# card.net
KiCad netlist of a schematic drawn in EasyEDA Pro
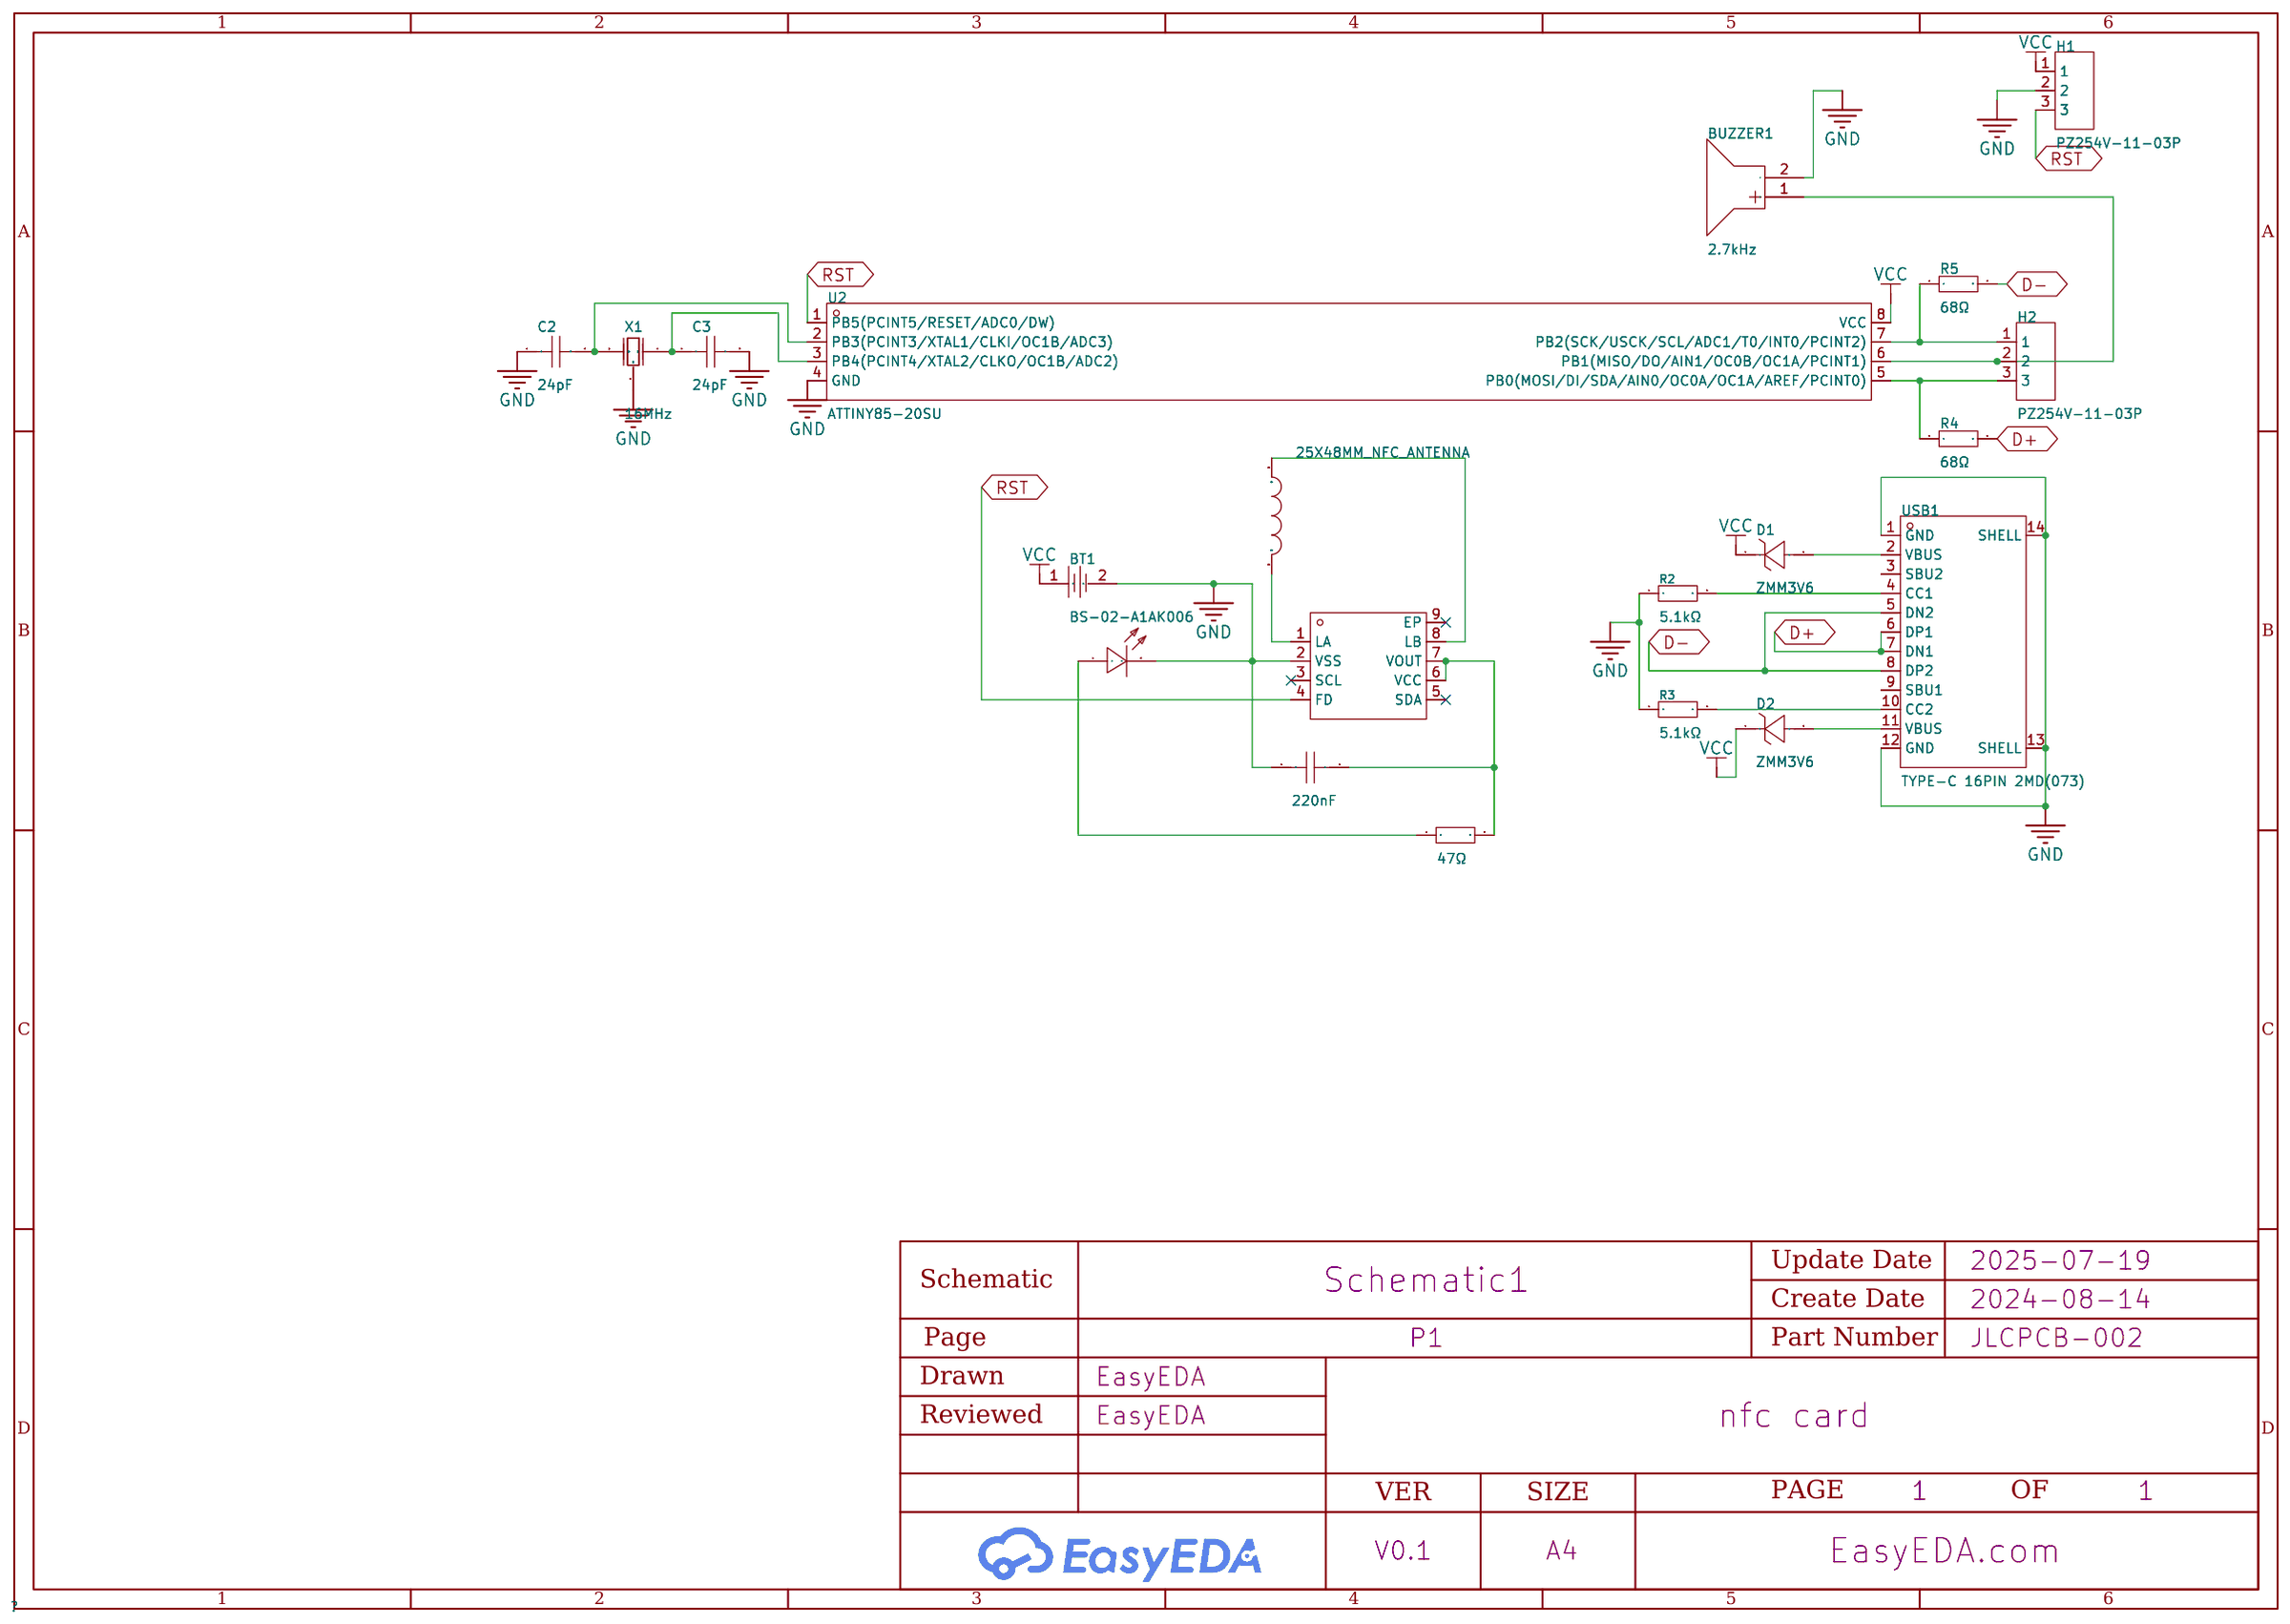
[diagram p0: schematic sheet]

(export (version "E")
  (design (tool "Eeschema 10.0.6"))
  (components
    (comp (ref "1") (value "25X48MM_NFC_ANTENNA") (libsource (lib "easyedapro") (part "25X48MM_NFC_ANTENNA")))
    (comp (ref "BT1")
      (value "BS-02-A1AK006")
      (footprint "easyedapro:BAT-TH_BS-02-A1AK006")
      (fields (field (name "Manufacturer") "MYOUNG(美阳)"))
      (libsource (lib "easyedapro") (part "BS-02-A1AK006"))
    )
    (comp (ref "BUZZER1")
      (value "2.7kHz")
      (footprint "easyedapro:BUZ-SMD_L9.6-W9.6-LS10.0-R")
      (fields
        (field (name "Manufacturer Part") "YS-SBZ9650DYB05")
        (field (name "Manufacturer") "Fengming(锋鸣电子)")
      )
      (libsource (lib "easyedapro") (part "YS-SBZ9650DYB05_C409830"))
    )
    (comp (ref "C1")
      (value "100nF")
      (footprint "easyedapro:C0805")
      (fields (field (name "Manufacturer Part") "C0805B104K500NT") (field (name "Manufacturer") "TORCH(火炬)"))
      (libsource (lib "easyedapro") (part "C0805B104K500NT"))
    )
    (comp (ref "C2")
      (value "24pF")
      (footprint "easyedapro:C0402")
      (description "Capacitance:24pF Tolerance:±5% Tolerance:±5% Voltage Rating:50V Temperature Coefficient:C0G")
      (fields
        (field (name "Manufacturer Part") "GJM1555C1H240JB01D")
        (field (name "Manufacturer") "muRata(村田)")
      )
      (libsource (lib "easyedapro") (part "GJM1555C1H240JB01D"))
    )
    (comp (ref "C3")
      (value "24pF")
      (footprint "easyedapro:C0402")
      (description "Capacitance:24pF Tolerance:±5% Tolerance:±5% Voltage Rating:50V Temperature Coefficient:C0G")
      (fields
        (field (name "Manufacturer Part") "GJM1555C1H240JB01D")
        (field (name "Manufacturer") "muRata(村田)")
      )
      (libsource (lib "easyedapro") (part "GJM1555C1H240JB01D"))
    )
    (comp (ref "D1")
      (value "ZMM3V6")
      (footprint "easyedapro:LL-34_L3.5-W1.5-RD")
      (fields (field (name "Manufacturer") "YONGYUTAI(永裕泰)"))
      (libsource (lib "easyedapro") (part "ZMM3V6_C2985635"))
    )
    (comp (ref "D2")
      (value "ZMM3V6")
      (footprint "easyedapro:LL-34_L3.5-W1.5-RD")
      (fields (field (name "Manufacturer") "YONGYUTAI(永裕泰)"))
      (libsource (lib "easyedapro") (part "ZMM3V6_C2985635"))
    )
    (comp (ref "H1")
      (value "PZ254V-11-03P")
      (footprint "easyedapro:HDR-TH_3P-P2.54-V-M")
      (fields (field (name "Manufacturer") "XFCN(兴飞)"))
      (libsource (lib "easyedapro") (part "PZ254V-11-03P"))
    )
    (comp (ref "H2")
      (value "PZ254V-11-03P")
      (footprint "easyedapro:HDR-TH_3P-P2.54-V-M")
      (fields (field (name "Manufacturer") "XFCN(兴飞)"))
      (libsource (lib "easyedapro") (part "PZ254V-11-03P"))
    )
    (comp (ref "LED1")
      (value "KT-0805YG")
      (footprint "easyedapro:LED0805-R-RD")
      (description "Emitted Color:Green-yellow")
      (fields (field (name "Manufacturer") "KENTO"))
      (libsource (lib "easyedapro") (part "Yellow green 0805"))
    )
    (comp (ref "R1")
      (value "47Ω")
      (footprint "easyedapro:R0805")
      (fields
        (field (name "Manufacturer Part") "0805W8F1002T5E")
        (field (name "Manufacturer") "UNI-ROYAL(厚声)")
      )
      (libsource (lib "easyedapro") (part "0805W8F1002T5E"))
    )
    (comp (ref "R2")
      (value "5.1kΩ")
      (footprint "easyedapro:R0402")
      (fields
        (field (name "Manufacturer Part") "0402WGF5101TCE")
        (field (name "Manufacturer") "UNI-ROYAL(厚声)")
      )
      (libsource (lib "easyedapro") (part "0402WGF5101TCE"))
    )
    (comp (ref "R3")
      (value "5.1kΩ")
      (footprint "easyedapro:R0402")
      (fields
        (field (name "Manufacturer Part") "0402WGF5101TCE")
        (field (name "Manufacturer") "UNI-ROYAL(厚声)")
      )
      (libsource (lib "easyedapro") (part "0402WGF5101TCE"))
    )
    (comp (ref "R4")
      (value "68Ω")
      (footprint "easyedapro:R0402")
      (fields (field (name "Manufacturer Part") "RC0402FR-0768RL") (field (name "Manufacturer") "YAGEO(国巨)"))
      (libsource (lib "easyedapro") (part "RC0402FR-0768RL"))
    )
    (comp (ref "R5")
      (value "68Ω")
      (footprint "easyedapro:R0402")
      (fields (field (name "Manufacturer Part") "RC0402FR-0768RL") (field (name "Manufacturer") "YAGEO(国巨)"))
      (libsource (lib "easyedapro") (part "RC0402FR-0768RL"))
    )
    (comp (ref "U1")
      (value "13.56MHz")
      (footprint "easyedapro:XQFN-8_L1.6-W1.6-P0.50-BL")
      (fields (field (name "Manufacturer Part") "NT3H2111W0FHKH") (field (name "Manufacturer") "NXP(恩智浦)"))
      (libsource (lib "easyedapro") (part "NT3H2111W0FHKH"))
    )
    (comp (ref "U2")
      (value "ATTINY85-20SU")
      (footprint "easyedapro:SOIC-8_L5.3-W5.3-P1.27-LS8.0-BL")
      (fields (field (name "Manufacturer") "MICROCHIP(美国微芯)"))
      (libsource (lib "easyedapro") (part "ATTINY85-20SU_C31540447"))
    )
    (comp (ref "USB1")
      (value "TYPE-C 16PIN 2MD(073)")
      (footprint "easyedapro:USB-C-SMD_TYPE-C-6PIN-2MD-073")
      (fields (field (name "Manufacturer") "SHOU HAN(首韩)"))
      (libsource (lib "easyedapro") (part "TYPE-C 16PIN 2MD(073)"))
    )
    (comp (ref "X1")
      (value "16MHz")
      (footprint "easyedapro:OSC-SMD_3P-L3.2-W1.3-P1.2-L")
      (fields
        (field (name "Manufacturer Part") "CSTNE16M0V530000R0")
        (field (name "Manufacturer") "muRata(村田)")
      )
      (libsource (lib "easyedapro") (part "CSTNE16M0V530000R0"))
    )
  )
  (nets
    (net (code "1") (name "D+") (class "Default")
      (node (ref "R4") (pin "2") (pinfunction "2_2") (pintype "input"))
      (node (ref "USB1") (pin "6") (pinfunction "DP1_6") (pintype "unspecified"))
      (node (ref "USB1") (pin "7") (pinfunction "DN1_7") (pintype "unspecified"))
    )
    (net (code "2") (name "D-") (class "Default")
      (node (ref "R5") (pin "2") (pinfunction "2_2") (pintype "input"))
      (node (ref "USB1") (pin "5") (pinfunction "DN2_5") (pintype "unspecified"))
      (node (ref "USB1") (pin "8") (pinfunction "DP2_8") (pintype "unspecified"))
    )
    (net (code "3") (name "GND") (class "Default")
      (node (ref "BT1") (pin "2") (pinfunction "2_2") (pintype "input"))
      (node (ref "BUZZER1") (pin "2") (pinfunction "-_2") (pintype "unspecified"))
      (node (ref "C1") (pin "1") (pinfunction "1_1") (pintype "input"))
      (node (ref "C2") (pin "1") (pinfunction "1_1") (pintype "unspecified"))
      (node (ref "C3") (pin "2") (pinfunction "2_2") (pintype "unspecified"))
      (node (ref "H1") (pin "2") (pinfunction "2_2") (pintype "unspecified"))
      (node (ref "LED1") (pin "2") (pinfunction "K_2") (pintype "unspecified"))
      (node (ref "R2") (pin "1") (pinfunction "1_1") (pintype "input"))
      (node (ref "R3") (pin "1") (pinfunction "1_1") (pintype "input"))
      (node (ref "U1") (pin "2") (pinfunction "VSS_2") (pintype "unspecified"))
      (node (ref "U2") (pin "4") (pinfunction "GND_4") (pintype "unspecified"))
      (node (ref "USB1") (pin "1") (pinfunction "GND_1") (pintype "unspecified"))
      (node (ref "USB1") (pin "12") (pinfunction "GND_12") (pintype "unspecified"))
      (node (ref "USB1") (pin "13") (pinfunction "SHELL_13") (pintype "unspecified"))
      (node (ref "USB1") (pin "14") (pinfunction "SHELL_14") (pintype "unspecified"))
      (node (ref "X1") (pin "2") (pinfunction "GND_2") (pintype "input"))
    )
    (net (code "4") (name "Net-(BUZZER1-+)") (class "Default")
      (node (ref "BUZZER1") (pin "1") (pinfunction "+_1") (pintype "unspecified"))
      (node (ref "H2") (pin "2") (pinfunction "2_2") (pintype "unspecified"))
      (node (ref "U2") (pin "6") (pinfunction "PB1(MISO/DO/AIN1/OC0B/OC1A/PCINT1)_6") (pintype "unspecified"))
    )
    (net (code "5") (name "Net-(D1-A)") (class "Default")
      (node (ref "D1") (pin "2") (pinfunction "A_2") (pintype "unspecified"))
      (node (ref "USB1") (pin "2") (pinfunction "VBUS_2") (pintype "unspecified"))
    )
    (net (code "6") (name "Net-(D2-A)") (class "Default")
      (node (ref "D2") (pin "2") (pinfunction "A_2") (pintype "unspecified"))
      (node (ref "USB1") (pin "11") (pinfunction "VBUS_11") (pintype "unspecified"))
    )
    (net (code "7") (name "Net-(LED1-A)") (class "Default")
      (node (ref "LED1") (pin "1") (pinfunction "A_1") (pintype "unspecified"))
      (node (ref "R1") (pin "1") (pinfunction "1_1") (pintype "input"))
    )
    (net (code "8") (name "Net-(U1-LA)") (class "Default")
      (node (ref "1") (pin "P$2") (pinfunction "P$2_P$2") (pintype "bidirectional"))
      (node (ref "U1") (pin "1") (pinfunction "LA_1") (pintype "unspecified"))
    )
    (net (code "9") (name "Net-(U1-LB)") (class "Default")
      (node (ref "1") (pin "P$1") (pinfunction "P$1_P$1") (pintype "bidirectional"))
      (node (ref "U1") (pin "8") (pinfunction "LB_8") (pintype "unspecified"))
    )
    (net (code "10") (name "Net-(U1-VCC)") (class "Default")
      (node (ref "C1") (pin "2") (pinfunction "2_2") (pintype "input"))
      (node (ref "R1") (pin "2") (pinfunction "2_2") (pintype "input"))
      (node (ref "U1") (pin "6") (pinfunction "VCC_6") (pintype "unspecified"))
      (node (ref "U1") (pin "7") (pinfunction "VOUT_7") (pintype "unspecified"))
    )
    (net (code "11") (name "Net-(U2-PB0(MOSI{slash}DI{slash}SDA{slash}AIN0{slash}OC0A{slash}OC1A{slash}AREF{slash}PCINT0))") (class "Default")
      (node (ref "H2") (pin "3") (pinfunction "3_3") (pintype "unspecified"))
      (node (ref "R4") (pin "1") (pinfunction "1_1") (pintype "input"))
      (node (ref "U2") (pin "5") (pinfunction "PB0(MOSI/DI/SDA/AIN0/OC0A/OC1A/AREF/PCINT0)_5") (pintype "unspecified"))
    )
    (net (code "12") (name "Net-(U2-PB2(SCK{slash}USCK{slash}SCL{slash}ADC1{slash}T0{slash}INT0{slash}PCINT2))") (class "Default")
      (node (ref "H2") (pin "1") (pinfunction "1_1") (pintype "unspecified"))
      (node (ref "R5") (pin "1") (pinfunction "1_1") (pintype "input"))
      (node (ref "U2") (pin "7") (pinfunction "PB2(SCK/USCK/SCL/ADC1/T0/INT0/PCINT2)_7") (pintype "unspecified"))
    )
    (net (code "13") (name "Net-(U2-PB3(PCINT3{slash}XTAL1{slash}CLKI{slash}OC1B{slash}ADC3))") (class "Default")
      (node (ref "C2") (pin "2") (pinfunction "2_2") (pintype "unspecified"))
      (node (ref "U2") (pin "2") (pinfunction "PB3(PCINT3/XTAL1/CLKI/OC1B/ADC3)_2") (pintype "unspecified"))
      (node (ref "X1") (pin "3") (pinfunction "OSC2_3") (pintype "input"))
    )
    (net (code "14") (name "Net-(U2-PB4(PCINT4{slash}XTAL2{slash}CLKO{slash}OC1B{slash}ADC2))") (class "Default")
      (node (ref "C3") (pin "1") (pinfunction "1_1") (pintype "unspecified"))
      (node (ref "U2") (pin "3") (pinfunction "PB4(PCINT4/XTAL2/CLKO/OC1B/ADC2)_3") (pintype "unspecified"))
      (node (ref "X1") (pin "1") (pinfunction "OSC1_1") (pintype "input"))
    )
    (net (code "15") (name "Net-(USB1-CC1)") (class "Default")
      (node (ref "R2") (pin "2") (pinfunction "2_2") (pintype "input"))
      (node (ref "USB1") (pin "4") (pinfunction "CC1_4") (pintype "unspecified"))
    )
    (net (code "16") (name "Net-(USB1-CC2)") (class "Default")
      (node (ref "R3") (pin "2") (pinfunction "2_2") (pintype "input"))
      (node (ref "USB1") (pin "10") (pinfunction "CC2_10") (pintype "unspecified"))
    )
    (net (code "17") (name "RST") (class "Default")
      (node (ref "H1") (pin "3") (pinfunction "3_3") (pintype "unspecified"))
      (node (ref "U1") (pin "4") (pinfunction "FD_4") (pintype "unspecified"))
      (node (ref "U2") (pin "1") (pinfunction "PB5(PCINT5/RESET/ADC0/DW)_1") (pintype "unspecified"))
    )
    (net (code "18") (name "VCC") (class "Default")
      (node (ref "BT1") (pin "1") (pinfunction "1_1") (pintype "input"))
      (node (ref "D1") (pin "1") (pinfunction "K_1") (pintype "unspecified"))
      (node (ref "D2") (pin "1") (pinfunction "K_1") (pintype "unspecified"))
      (node (ref "H1") (pin "1") (pinfunction "1_1") (pintype "unspecified"))
      (node (ref "U2") (pin "8") (pinfunction "VCC_8") (pintype "unspecified"))
    )
    (net (code "19") (name "unconnected-(U1-EP-Pad9)") (class "Default")
      (node (ref "U1") (pin "9") (pinfunction "EP_9") (pintype "unspecified+no_connect"))
    )
    (net (code "20") (name "unconnected-(U1-SCL-Pad3)") (class "Default")
      (node (ref "U1") (pin "3") (pinfunction "SCL_3") (pintype "unspecified+no_connect"))
    )
    (net (code "21") (name "unconnected-(U1-SDA-Pad5)") (class "Default")
      (node (ref "U1") (pin "5") (pinfunction "SDA_5") (pintype "unspecified+no_connect"))
    )
    (net (code "22") (name "unconnected-(USB1-SBU1-Pad9)") (class "Default")
      (node (ref "USB1") (pin "9") (pinfunction "SBU1_9") (pintype "unspecified"))
    )
    (net (code "23") (name "unconnected-(USB1-SBU2-Pad3)") (class "Default")
      (node (ref "USB1") (pin "3") (pinfunction "SBU2_3") (pintype "unspecified"))
    )
  )
)
